# relay_AZ832P2_THT.net
KiCad netlist of a schematic drawn in EAGLE
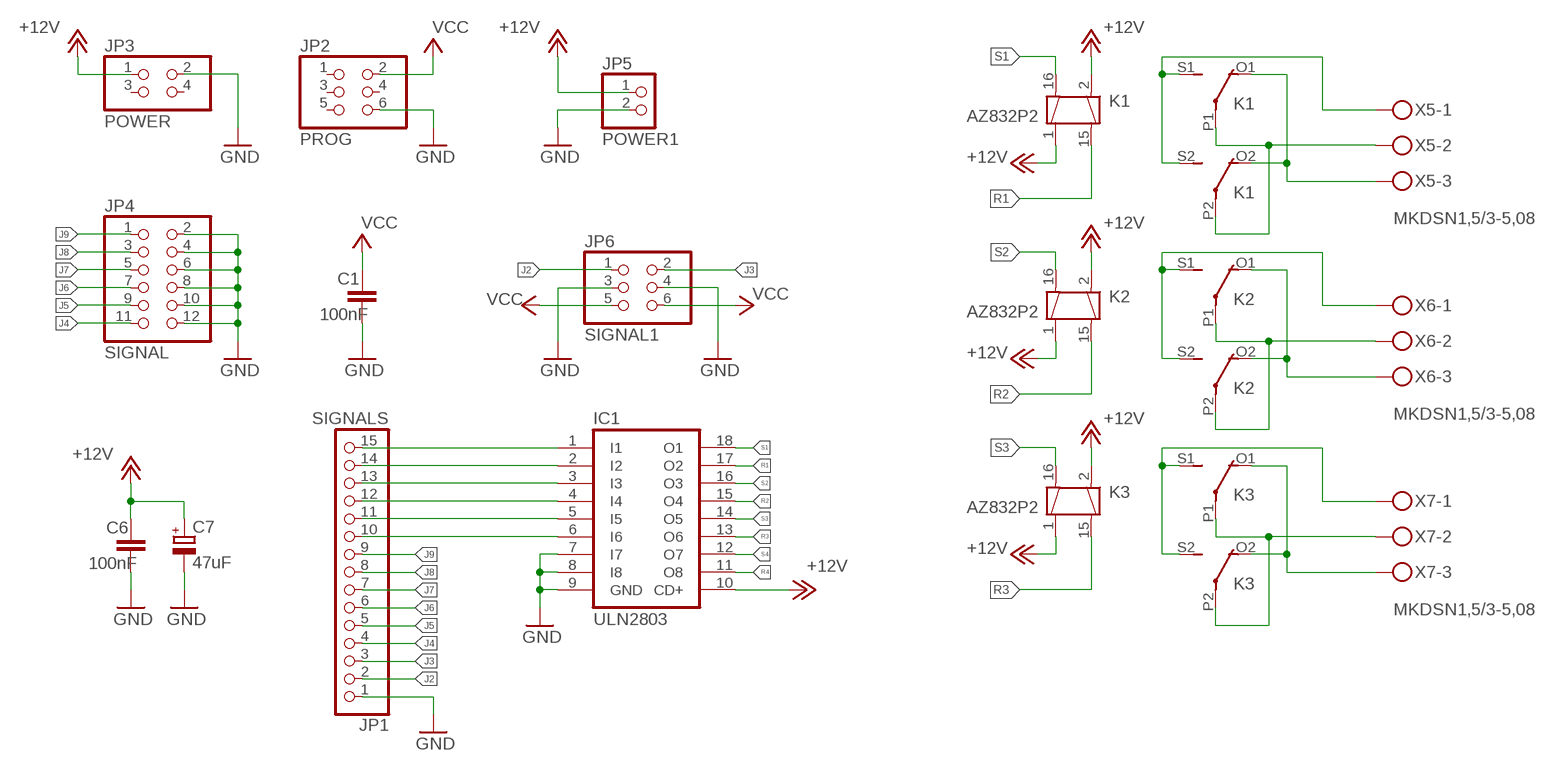
[diagram p0: schematic, sheet 1]

(export (version "E")
  (design (tool "Eeschema 10.0.6"))
  (components
    (comp (ref "C1")
      (value "100nF")
      (footprint "eagle-import:C025-025X050")
      (libsource (lib "eagle-import") (part "C-EU025-025X050"))
    )
    (comp (ref "C6")
      (value "100nF")
      (footprint "eagle-import:C025-025X050")
      (libsource (lib "eagle-import") (part "C-EU025-025X050"))
    )
    (comp (ref "C7")
      (value "47uF")
      (footprint "eagle-import:E2,5-6")
      (libsource (lib "eagle-import") (part "CPOL-EUE2.5-6"))
    )
    (comp (ref "IC1")
      (value "ULN2803")
      (footprint "eagle-import:DIL18")
      (libsource (lib "eagle-import") (part "ULN2803A"))
    )
    (comp (ref "JP1")
      (value "SIGNALS")
      (footprint "eagle-import:1X15")
      (libsource (lib "eagle-import") (part "PINHD-1X15"))
    )
    (comp (ref "JP2")
      (value "PROG")
      (footprint "eagle-import:2X03")
      (libsource (lib "eagle-import") (part "PINHD-2X3"))
    )
    (comp (ref "JP3")
      (value "POWER")
      (footprint "eagle-import:2X02")
      (libsource (lib "eagle-import") (part "PINHD-2X2"))
    )
    (comp (ref "JP4")
      (value "SIGNAL")
      (footprint "eagle-import:2X06")
      (libsource (lib "eagle-import") (part "PINHD-2X6"))
    )
    (comp (ref "JP5")
      (value "POWER1")
      (footprint "eagle-import:1X02")
      (libsource (lib "eagle-import") (part "PINHD-1X2"))
    )
    (comp (ref "JP6")
      (value "SIGNAL1")
      (footprint "eagle-import:2X03")
      (libsource (lib "eagle-import") (part "PINHD-2X3"))
    )
    (comp (ref "K1")
      (value "AZ832P2")
      (footprint "eagle-import:DS2E-L2")
      (libsource (lib "eagle-import") (part "DS2-L2-24V"))
    )
    (comp (ref "K2")
      (value "AZ832P2")
      (footprint "eagle-import:DS2E-L2")
      (libsource (lib "eagle-import") (part "DS2-L2-24V"))
    )
    (comp (ref "K3")
      (value "AZ832P2")
      (footprint "eagle-import:DS2E-L2")
      (libsource (lib "eagle-import") (part "DS2-L2-24V"))
    )
    (comp (ref "X5")
      (value "MKDSN1,5/3-5,08")
      (footprint "eagle-import:MKDSN1,5_3-5,08")
      (fields (field (name "MPN") "SMKDSN1,5/3-5,08"))
      (libsource (lib "eagle-import") (part "MKDSN1,5/3-5,08"))
    )
    (comp (ref "X6")
      (value "MKDSN1,5/3-5,08")
      (footprint "eagle-import:MKDSN1,5_3-5,08")
      (fields (field (name "MPN") "SMKDSN1,5/3-5,08"))
      (libsource (lib "eagle-import") (part "MKDSN1,5/3-5,08"))
    )
    (comp (ref "X7")
      (value "MKDSN1,5/3-5,08")
      (footprint "eagle-import:MKDSN1,5_3-5,08")
      (fields (field (name "MPN") "SMKDSN1,5/3-5,08"))
      (libsource (lib "eagle-import") (part "MKDSN1,5/3-5,08"))
    )
  )
  (nets
    (net (code "1") (name "+12V") (class "Default")
      (node (ref "C6") (pin "1") (pinfunction "1_1") (pintype "passive"))
      (node (ref "C7") (pin "+") (pinfunction "+_+") (pintype "passive"))
      (node (ref "IC1") (pin "10") (pinfunction "CD+_10") (pintype "passive"))
      (node (ref "JP3") (pin "1") (pinfunction "1_1") (pintype "passive"))
      (node (ref "JP5") (pin "1") (pinfunction "1_1") (pintype "passive"))
      (node (ref "K1") (pin "1") (pinfunction "2_1") (pintype "passive"))
      (node (ref "K1") (pin "2") (pinfunction "3_2") (pintype "passive"))
      (node (ref "K2") (pin "1") (pinfunction "2_1") (pintype "passive"))
      (node (ref "K2") (pin "2") (pinfunction "3_2") (pintype "passive"))
      (node (ref "K3") (pin "1") (pinfunction "2_1") (pintype "passive"))
      (node (ref "K3") (pin "2") (pinfunction "3_2") (pintype "passive"))
    )
    (net (code "2") (name "GND") (class "Default")
      (node (ref "C1") (pin "2") (pinfunction "2_2") (pintype "passive"))
      (node (ref "C6") (pin "2") (pinfunction "2_2") (pintype "passive"))
      (node (ref "C7") (pin "-") (pinfunction "-_-") (pintype "passive"))
      (node (ref "IC1") (pin "7") (pinfunction "I7_7") (pintype "input"))
      (node (ref "IC1") (pin "8") (pinfunction "I8_8") (pintype "input"))
      (node (ref "IC1") (pin "9") (pinfunction "GND_9") (pintype "power_in"))
      (node (ref "JP1") (pin "1") (pinfunction "1_1") (pintype "passive"))
      (node (ref "JP2") (pin "6") (pinfunction "6_6") (pintype "passive"))
      (node (ref "JP3") (pin "2") (pinfunction "2_2") (pintype "passive"))
      (node (ref "JP4") (pin "10") (pinfunction "10_10") (pintype "passive"))
      (node (ref "JP4") (pin "12") (pinfunction "12_12") (pintype "passive"))
      (node (ref "JP4") (pin "2") (pinfunction "2_2") (pintype "passive"))
      (node (ref "JP4") (pin "4") (pinfunction "4_4") (pintype "passive"))
      (node (ref "JP4") (pin "6") (pinfunction "6_6") (pintype "passive"))
      (node (ref "JP4") (pin "8") (pinfunction "8_8") (pintype "passive"))
      (node (ref "JP5") (pin "2") (pinfunction "2_2") (pintype "passive"))
      (node (ref "JP6") (pin "3") (pinfunction "3_3") (pintype "passive"))
      (node (ref "JP6") (pin "4") (pinfunction "4_4") (pintype "passive"))
    )
    (net (code "3") (name "J2") (class "Default")
      (node (ref "JP1") (pin "2") (pinfunction "2_2") (pintype "passive"))
      (node (ref "JP6") (pin "1") (pinfunction "1_1") (pintype "passive"))
    )
    (net (code "4") (name "J3") (class "Default")
      (node (ref "JP1") (pin "3") (pinfunction "3_3") (pintype "passive"))
      (node (ref "JP6") (pin "2") (pinfunction "2_2") (pintype "passive"))
    )
    (net (code "5") (name "J4") (class "Default")
      (node (ref "JP1") (pin "4") (pinfunction "4_4") (pintype "passive"))
      (node (ref "JP4") (pin "11") (pinfunction "11_11") (pintype "passive"))
    )
    (net (code "6") (name "J5") (class "Default")
      (node (ref "JP1") (pin "5") (pinfunction "5_5") (pintype "passive"))
      (node (ref "JP4") (pin "9") (pinfunction "9_9") (pintype "passive"))
    )
    (net (code "7") (name "J6") (class "Default")
      (node (ref "JP1") (pin "6") (pinfunction "6_6") (pintype "passive"))
      (node (ref "JP4") (pin "7") (pinfunction "7_7") (pintype "passive"))
    )
    (net (code "8") (name "J7") (class "Default")
      (node (ref "JP1") (pin "7") (pinfunction "7_7") (pintype "passive"))
      (node (ref "JP4") (pin "5") (pinfunction "5_5") (pintype "passive"))
    )
    (net (code "9") (name "J8") (class "Default")
      (node (ref "JP1") (pin "8") (pinfunction "8_8") (pintype "passive"))
      (node (ref "JP4") (pin "3") (pinfunction "3_3") (pintype "passive"))
    )
    (net (code "10") (name "J9") (class "Default")
      (node (ref "JP1") (pin "9") (pinfunction "9_9") (pintype "passive"))
      (node (ref "JP4") (pin "1") (pinfunction "1_1") (pintype "passive"))
    )
    (net (code "11") (name "Net-(IC1-I1)") (class "Default")
      (node (ref "IC1") (pin "1") (pinfunction "I1_1") (pintype "input"))
      (node (ref "JP1") (pin "15") (pinfunction "15_15") (pintype "passive"))
    )
    (net (code "12") (name "Net-(IC1-I2)") (class "Default")
      (node (ref "IC1") (pin "2") (pinfunction "I2_2") (pintype "input"))
      (node (ref "JP1") (pin "14") (pinfunction "14_14") (pintype "passive"))
    )
    (net (code "13") (name "Net-(IC1-I3)") (class "Default")
      (node (ref "IC1") (pin "3") (pinfunction "I3_3") (pintype "input"))
      (node (ref "JP1") (pin "13") (pinfunction "13_13") (pintype "passive"))
    )
    (net (code "14") (name "Net-(IC1-I4)") (class "Default")
      (node (ref "IC1") (pin "4") (pinfunction "I4_4") (pintype "input"))
      (node (ref "JP1") (pin "12") (pinfunction "12_12") (pintype "passive"))
    )
    (net (code "15") (name "Net-(IC1-I5)") (class "Default")
      (node (ref "IC1") (pin "5") (pinfunction "I5_5") (pintype "input"))
      (node (ref "JP1") (pin "11") (pinfunction "11_11") (pintype "passive"))
    )
    (net (code "16") (name "Net-(IC1-I6)") (class "Default")
      (node (ref "IC1") (pin "6") (pinfunction "I6_6") (pintype "input"))
      (node (ref "JP1") (pin "10") (pinfunction "10_10") (pintype "passive"))
    )
    (net (code "17") (name "Net-(K1B-O)") (class "Default")
      (node (ref "K1") (pin "O1") (pinfunction "O_O1") (pintype "passive"))
      (node (ref "K1") (pin "O2") (pinfunction "O_O2") (pintype "passive"))
      (node (ref "X5") (pin "3") (pinfunction "KL_3") (pintype "passive"))
    )
    (net (code "18") (name "Net-(K1B-P)") (class "Default")
      (node (ref "K1") (pin "P1") (pinfunction "P_P1") (pintype "passive"))
      (node (ref "K1") (pin "P2") (pinfunction "P_P2") (pintype "passive"))
      (node (ref "X5") (pin "2") (pinfunction "KL_2") (pintype "passive"))
    )
    (net (code "19") (name "Net-(K1B-S)") (class "Default")
      (node (ref "K1") (pin "S1") (pinfunction "S_S1") (pintype "passive"))
      (node (ref "K1") (pin "S2") (pinfunction "S_S2") (pintype "passive"))
      (node (ref "X5") (pin "1") (pinfunction "KL_1") (pintype "passive"))
    )
    (net (code "20") (name "Net-(K2B-O)") (class "Default")
      (node (ref "K2") (pin "O1") (pinfunction "O_O1") (pintype "passive"))
      (node (ref "K2") (pin "O2") (pinfunction "O_O2") (pintype "passive"))
      (node (ref "X6") (pin "3") (pinfunction "KL_3") (pintype "passive"))
    )
    (net (code "21") (name "Net-(K2B-P)") (class "Default")
      (node (ref "K2") (pin "P1") (pinfunction "P_P1") (pintype "passive"))
      (node (ref "K2") (pin "P2") (pinfunction "P_P2") (pintype "passive"))
      (node (ref "X6") (pin "2") (pinfunction "KL_2") (pintype "passive"))
    )
    (net (code "22") (name "Net-(K2B-S)") (class "Default")
      (node (ref "K2") (pin "S1") (pinfunction "S_S1") (pintype "passive"))
      (node (ref "K2") (pin "S2") (pinfunction "S_S2") (pintype "passive"))
      (node (ref "X6") (pin "1") (pinfunction "KL_1") (pintype "passive"))
    )
    (net (code "23") (name "Net-(K3B-O)") (class "Default")
      (node (ref "K3") (pin "O1") (pinfunction "O_O1") (pintype "passive"))
      (node (ref "K3") (pin "O2") (pinfunction "O_O2") (pintype "passive"))
      (node (ref "X7") (pin "3") (pinfunction "KL_3") (pintype "passive"))
    )
    (net (code "24") (name "Net-(K3B-P)") (class "Default")
      (node (ref "K3") (pin "P1") (pinfunction "P_P1") (pintype "passive"))
      (node (ref "K3") (pin "P2") (pinfunction "P_P2") (pintype "passive"))
      (node (ref "X7") (pin "2") (pinfunction "KL_2") (pintype "passive"))
    )
    (net (code "25") (name "Net-(K3B-S)") (class "Default")
      (node (ref "K3") (pin "S1") (pinfunction "S_S1") (pintype "passive"))
      (node (ref "K3") (pin "S2") (pinfunction "S_S2") (pintype "passive"))
      (node (ref "X7") (pin "1") (pinfunction "KL_1") (pintype "passive"))
    )
    (net (code "26") (name "R1") (class "Default")
      (node (ref "IC1") (pin "17") (pinfunction "O2_17") (pintype "open_collector"))
      (node (ref "K1") (pin "15") (pinfunction "4_15") (pintype "passive"))
    )
    (net (code "27") (name "R2") (class "Default")
      (node (ref "IC1") (pin "15") (pinfunction "O4_15") (pintype "open_collector"))
      (node (ref "K2") (pin "15") (pinfunction "4_15") (pintype "passive"))
    )
    (net (code "28") (name "R3") (class "Default")
      (node (ref "IC1") (pin "13") (pinfunction "O6_13") (pintype "open_collector"))
      (node (ref "K3") (pin "15") (pinfunction "4_15") (pintype "passive"))
    )
    (net (code "29") (name "R4") (class "Default")
      (node (ref "IC1") (pin "11") (pinfunction "O8_11") (pintype "open_collector"))
    )
    (net (code "30") (name "S1") (class "Default")
      (node (ref "IC1") (pin "18") (pinfunction "O1_18") (pintype "open_collector"))
      (node (ref "K1") (pin "16") (pinfunction "1_16") (pintype "passive"))
    )
    (net (code "31") (name "S2") (class "Default")
      (node (ref "IC1") (pin "16") (pinfunction "O3_16") (pintype "open_collector"))
      (node (ref "K2") (pin "16") (pinfunction "1_16") (pintype "passive"))
    )
    (net (code "32") (name "S3") (class "Default")
      (node (ref "IC1") (pin "14") (pinfunction "O5_14") (pintype "open_collector"))
      (node (ref "K3") (pin "16") (pinfunction "1_16") (pintype "passive"))
    )
    (net (code "33") (name "S4") (class "Default")
      (node (ref "IC1") (pin "12") (pinfunction "O7_12") (pintype "open_collector"))
    )
    (net (code "34") (name "VCC") (class "Default")
      (node (ref "C1") (pin "1") (pinfunction "1_1") (pintype "passive"))
      (node (ref "JP2") (pin "2") (pinfunction "2_2") (pintype "passive"))
      (node (ref "JP6") (pin "5") (pinfunction "5_5") (pintype "passive"))
      (node (ref "JP6") (pin "6") (pinfunction "6_6") (pintype "passive"))
    )
    (net (code "35") (name "unconnected-(JP2-Pad1)") (class "Default")
      (node (ref "JP2") (pin "1") (pinfunction "1_1") (pintype "passive"))
    )
    (net (code "36") (name "unconnected-(JP2-Pad3)") (class "Default")
      (node (ref "JP2") (pin "3") (pinfunction "3_3") (pintype "passive"))
    )
    (net (code "37") (name "unconnected-(JP2-Pad4)") (class "Default")
      (node (ref "JP2") (pin "4") (pinfunction "4_4") (pintype "passive"))
    )
    (net (code "38") (name "unconnected-(JP2-Pad5)") (class "Default")
      (node (ref "JP2") (pin "5") (pinfunction "5_5") (pintype "passive"))
    )
    (net (code "39") (name "unconnected-(JP3-Pad3)") (class "Default")
      (node (ref "JP3") (pin "3") (pinfunction "3_3") (pintype "passive"))
    )
    (net (code "40") (name "unconnected-(JP3-Pad4)") (class "Default")
      (node (ref "JP3") (pin "4") (pinfunction "4_4") (pintype "passive"))
    )
  )
)
